# Sur_control.net
KiCad netlist of a schematic drawn in EAGLE
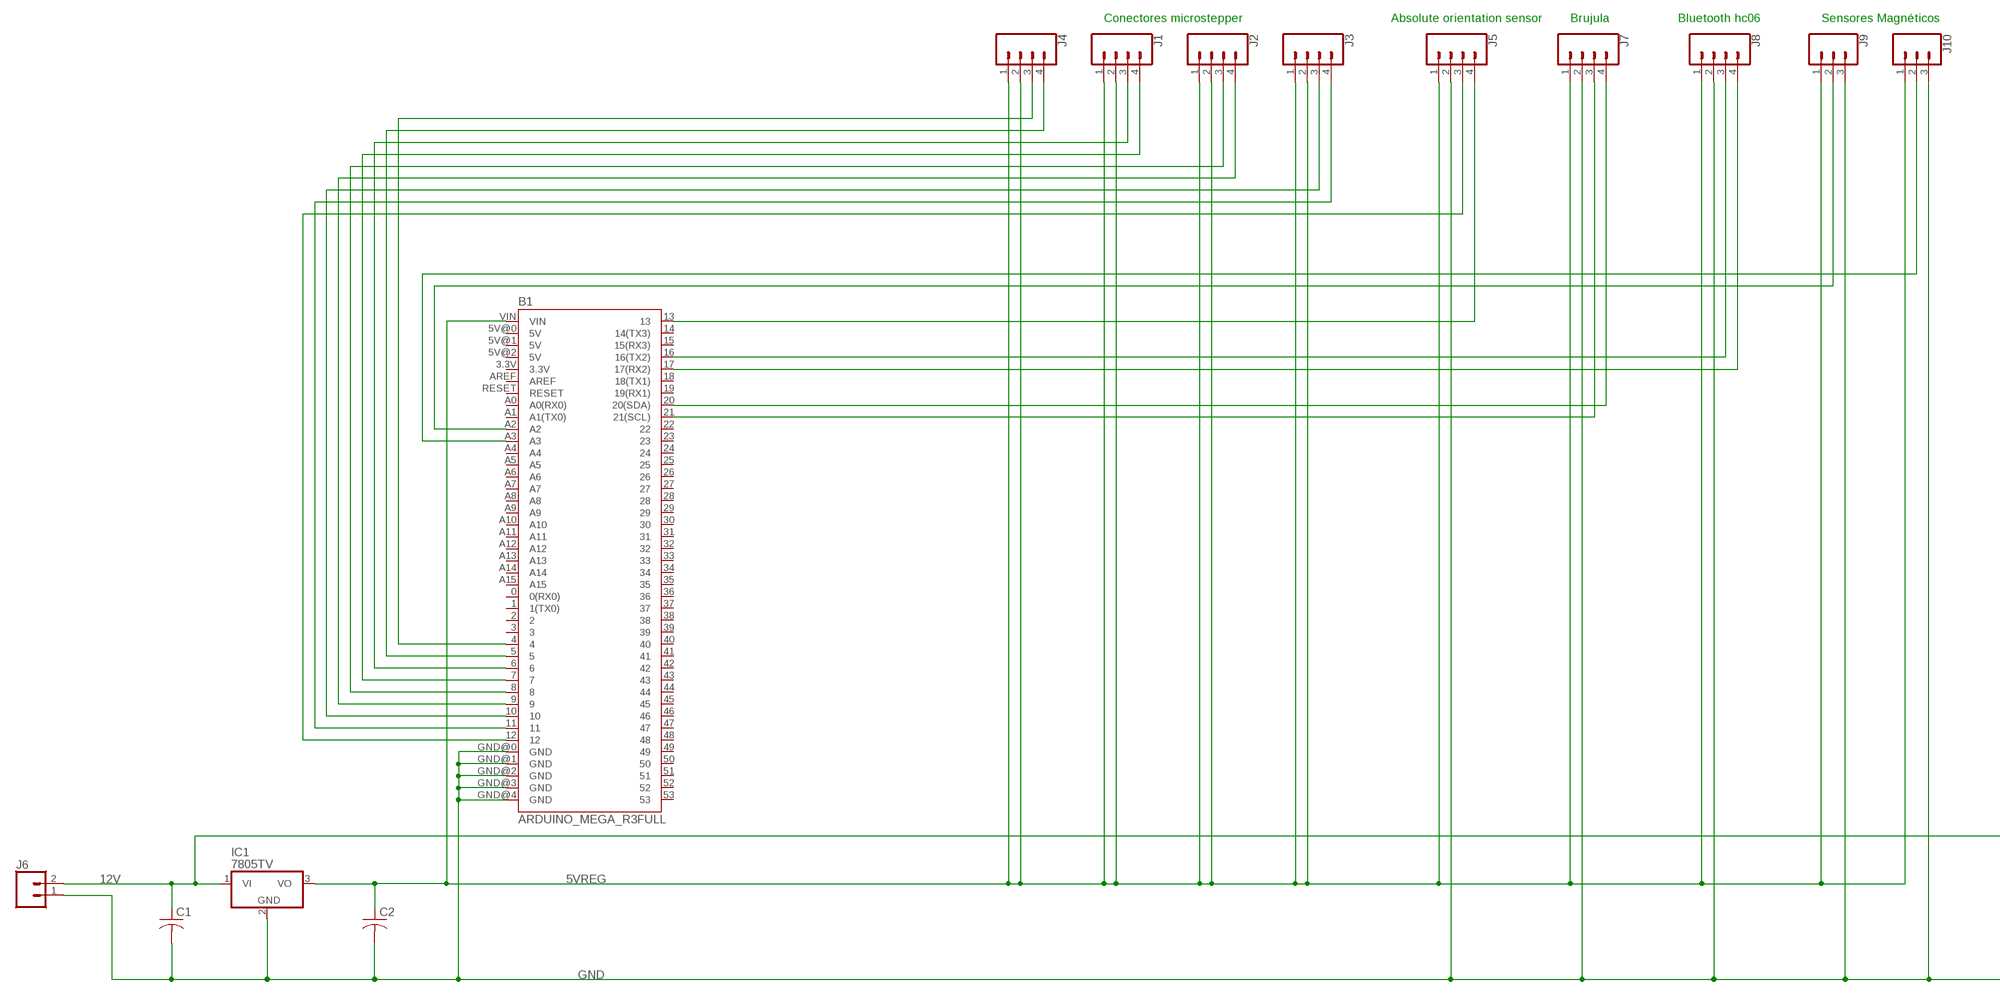
[diagram p0: schematic, sheet 1, part 1 of 2]
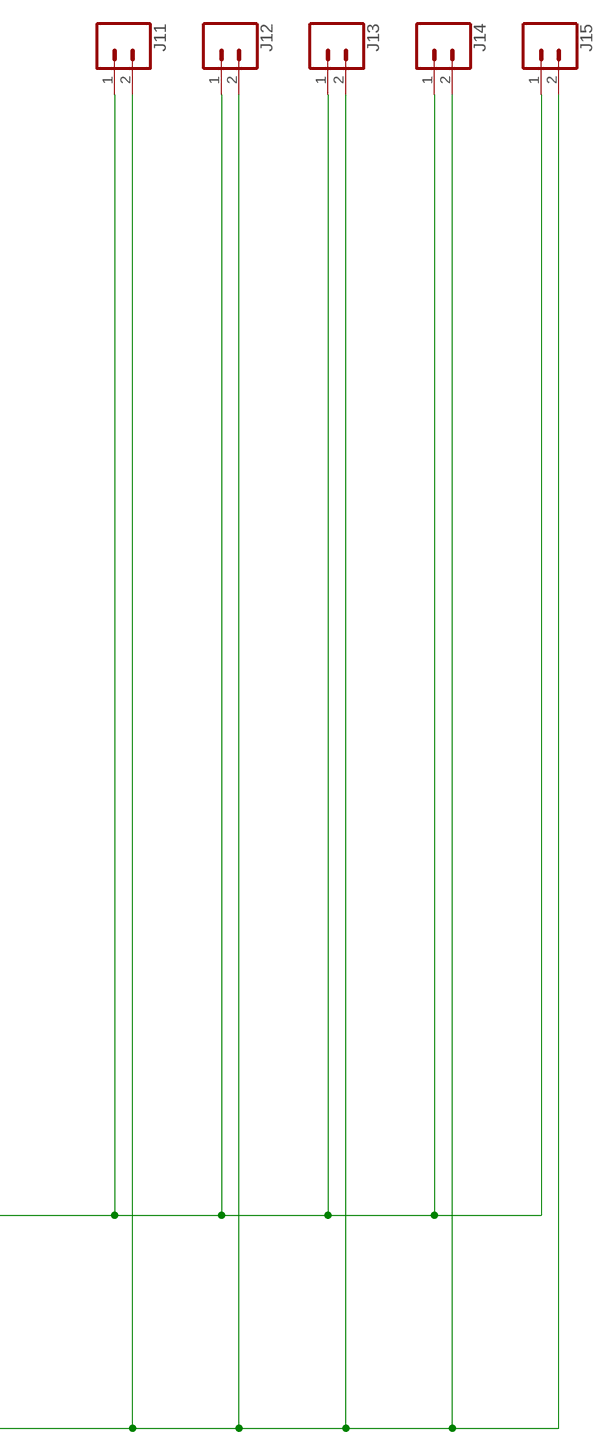
[diagram p1: schematic, sheet 1, part 2 of 2]

(export (version "E")
  (design (tool "Eeschema 10.0.6"))
  (components
    (comp (ref "B1")
      (value "ARDUINO_MEGA_R3FULL")
      (footprint "eagle-import:ARDUINO_MEGA")
      (libsource (lib "eagle-import") (part "ARDUINO_MEGA_R3FULL"))
    )
    (comp (ref "C1")
      (value "C-US050-025X075")
      (footprint "eagle-import:C050-025X075")
      (libsource (lib "eagle-import") (part "C-US050-025X075"))
    )
    (comp (ref "C2")
      (value "C-US050-025X075")
      (footprint "eagle-import:C050-025X075")
      (libsource (lib "eagle-import") (part "C-US050-025X075"))
    )
    (comp (ref "IC1")
      (value "7805TV")
      (footprint "eagle-import:TO220V")
      (libsource (lib "eagle-import") (part "78TV05"))
    )
    (comp (ref "J1")
      (value "CONN_04SCREW_LOCK")
      (footprint "eagle-import:SCREWTERMINAL-3.5MM-4_LOCK")
      (libsource (lib "eagle-import") (part "CONN_04SCREW_LOCK"))
    )
    (comp (ref "J2")
      (value "CONN_04SCREW_LOCK")
      (footprint "eagle-import:SCREWTERMINAL-3.5MM-4_LOCK")
      (libsource (lib "eagle-import") (part "CONN_04SCREW_LOCK"))
    )
    (comp (ref "J3")
      (value "CONN_04SCREW_LOCK")
      (footprint "eagle-import:SCREWTERMINAL-3.5MM-4_LOCK")
      (libsource (lib "eagle-import") (part "CONN_04SCREW_LOCK"))
    )
    (comp (ref "J4")
      (value "CONN_04SCREW_LOCK")
      (footprint "eagle-import:SCREWTERMINAL-3.5MM-4_LOCK")
      (libsource (lib "eagle-import") (part "CONN_04SCREW_LOCK"))
    )
    (comp (ref "J5")
      (value "CONN_04SCREW_LOCK")
      (footprint "eagle-import:SCREWTERMINAL-3.5MM-4_LOCK")
      (libsource (lib "eagle-import") (part "CONN_04SCREW_LOCK"))
    )
    (comp (ref "J6")
      (value "CONN_023.5MM_LOCK")
      (footprint "eagle-import:SCREWTERMINAL-3.5MM-2_LOCK")
      (libsource (lib "eagle-import") (part "CONN_023.5MM_LOCK"))
    )
    (comp (ref "J7")
      (value "CONN_04SCREW_LOCK")
      (footprint "eagle-import:SCREWTERMINAL-3.5MM-4_LOCK")
      (libsource (lib "eagle-import") (part "CONN_04SCREW_LOCK"))
    )
    (comp (ref "J8")
      (value "CONN_04SCREW_LOCK")
      (footprint "eagle-import:SCREWTERMINAL-3.5MM-4_LOCK")
      (libsource (lib "eagle-import") (part "CONN_04SCREW_LOCK"))
    )
    (comp (ref "J9")
      (value "CONN_03SCREW_LOCK")
      (footprint "eagle-import:SCREWTERMINAL-3.5MM-3_LOCK.007S")
      (libsource (lib "eagle-import") (part "CONN_03SCREW_LOCK"))
    )
    (comp (ref "J10")
      (value "CONN_03SCREW_LOCK")
      (footprint "eagle-import:SCREWTERMINAL-3.5MM-3_LOCK.007S")
      (libsource (lib "eagle-import") (part "CONN_03SCREW_LOCK"))
    )
    (comp (ref "J11")
      (value "CONN_023.5MM_LOCK")
      (footprint "eagle-import:SCREWTERMINAL-3.5MM-2_LOCK")
      (libsource (lib "eagle-import") (part "CONN_023.5MM_LOCK"))
    )
    (comp (ref "J12")
      (value "CONN_023.5MM_LOCK")
      (footprint "eagle-import:SCREWTERMINAL-3.5MM-2_LOCK")
      (libsource (lib "eagle-import") (part "CONN_023.5MM_LOCK"))
    )
    (comp (ref "J13")
      (value "CONN_023.5MM_LOCK")
      (footprint "eagle-import:SCREWTERMINAL-3.5MM-2_LOCK")
      (libsource (lib "eagle-import") (part "CONN_023.5MM_LOCK"))
    )
    (comp (ref "J14")
      (value "CONN_023.5MM_LOCK")
      (footprint "eagle-import:SCREWTERMINAL-3.5MM-2_LOCK")
      (libsource (lib "eagle-import") (part "CONN_023.5MM_LOCK"))
    )
    (comp (ref "J15")
      (value "CONN_023.5MM_LOCK")
      (footprint "eagle-import:SCREWTERMINAL-3.5MM-2_LOCK")
      (libsource (lib "eagle-import") (part "CONN_023.5MM_LOCK"))
    )
  )
  (nets
    (net (code "1") (name "/5VREG") (class "Default")
      (node (ref "B1") (pin "VIN") (pinfunction "VIN_VIN") (pintype "bidirectional"))
      (node (ref "C2") (pin "1") (pinfunction "1_1") (pintype "passive"))
      (node (ref "IC1") (pin "3") (pinfunction "VO_3") (pintype "passive"))
      (node (ref "J1") (pin "1") (pinfunction "1_1") (pintype "passive"))
      (node (ref "J1") (pin "2") (pinfunction "2_2") (pintype "passive"))
      (node (ref "J10") (pin "1") (pinfunction "1_1") (pintype "passive"))
      (node (ref "J2") (pin "1") (pinfunction "1_1") (pintype "passive"))
      (node (ref "J2") (pin "2") (pinfunction "2_2") (pintype "passive"))
      (node (ref "J3") (pin "1") (pinfunction "1_1") (pintype "passive"))
      (node (ref "J3") (pin "2") (pinfunction "2_2") (pintype "passive"))
      (node (ref "J4") (pin "1") (pinfunction "1_1") (pintype "passive"))
      (node (ref "J4") (pin "2") (pinfunction "2_2") (pintype "passive"))
      (node (ref "J5") (pin "1") (pinfunction "1_1") (pintype "passive"))
      (node (ref "J7") (pin "1") (pinfunction "1_1") (pintype "passive"))
      (node (ref "J8") (pin "1") (pinfunction "1_1") (pintype "passive"))
      (node (ref "J9") (pin "1") (pinfunction "1_1") (pintype "passive"))
    )
    (net (code "2") (name "/12V") (class "Default")
      (node (ref "C1") (pin "1") (pinfunction "1_1") (pintype "passive"))
      (node (ref "IC1") (pin "1") (pinfunction "VI_1") (pintype "input"))
      (node (ref "J11") (pin "1") (pinfunction "1_1") (pintype "passive"))
      (node (ref "J12") (pin "1") (pinfunction "1_1") (pintype "passive"))
      (node (ref "J13") (pin "1") (pinfunction "1_1") (pintype "passive"))
      (node (ref "J14") (pin "1") (pinfunction "1_1") (pintype "passive"))
      (node (ref "J15") (pin "1") (pinfunction "1_1") (pintype "passive"))
      (node (ref "J6") (pin "2") (pinfunction "2_2") (pintype "passive"))
    )
    (net (code "3") (name "/GND") (class "Default")
      (node (ref "B1") (pin "GND@0") (pinfunction "GND_GND@0") (pintype "bidirectional"))
      (node (ref "B1") (pin "GND@1") (pinfunction "GND_GND@1") (pintype "bidirectional"))
      (node (ref "B1") (pin "GND@2") (pinfunction "GND_GND@2") (pintype "bidirectional"))
      (node (ref "B1") (pin "GND@3") (pinfunction "GND_GND@3") (pintype "bidirectional"))
      (node (ref "B1") (pin "GND@4") (pinfunction "GND_GND@4") (pintype "bidirectional"))
      (node (ref "C1") (pin "2") (pinfunction "2_2") (pintype "passive"))
      (node (ref "C2") (pin "2") (pinfunction "2_2") (pintype "passive"))
      (node (ref "IC1") (pin "2") (pinfunction "GND_2") (pintype "passive"))
      (node (ref "J10") (pin "3") (pinfunction "3_3") (pintype "passive"))
      (node (ref "J11") (pin "2") (pinfunction "2_2") (pintype "passive"))
      (node (ref "J12") (pin "2") (pinfunction "2_2") (pintype "passive"))
      (node (ref "J13") (pin "2") (pinfunction "2_2") (pintype "passive"))
      (node (ref "J14") (pin "2") (pinfunction "2_2") (pintype "passive"))
      (node (ref "J15") (pin "2") (pinfunction "2_2") (pintype "passive"))
      (node (ref "J5") (pin "2") (pinfunction "2_2") (pintype "passive"))
      (node (ref "J6") (pin "1") (pinfunction "1_1") (pintype "passive"))
      (node (ref "J7") (pin "2") (pinfunction "2_2") (pintype "passive"))
      (node (ref "J8") (pin "2") (pinfunction "2_2") (pintype "passive"))
      (node (ref "J9") (pin "3") (pinfunction "3_3") (pintype "passive"))
    )
    (net (code "4") (name "Net-(B1-16(TX2))") (class "Default")
      (node (ref "B1") (pin "16") (pinfunction "16(TX2)_16") (pintype "bidirectional"))
      (node (ref "J8") (pin "3") (pinfunction "3_3") (pintype "passive"))
    )
    (net (code "5") (name "Net-(B1-17(RX2))") (class "Default")
      (node (ref "B1") (pin "17") (pinfunction "17(RX2)_17") (pintype "bidirectional"))
      (node (ref "J8") (pin "4") (pinfunction "4_4") (pintype "passive"))
    )
    (net (code "6") (name "Net-(B1-20(SDA))") (class "Default")
      (node (ref "B1") (pin "20") (pinfunction "20(SDA)_20") (pintype "bidirectional"))
      (node (ref "J7") (pin "4") (pinfunction "4_4") (pintype "passive"))
    )
    (net (code "7") (name "Net-(B1-21(SCL))") (class "Default")
      (node (ref "B1") (pin "21") (pinfunction "21(SCL)_21") (pintype "bidirectional"))
      (node (ref "J7") (pin "3") (pinfunction "3_3") (pintype "passive"))
    )
    (net (code "8") (name "Net-(B1-Pad4)") (class "Default")
      (node (ref "B1") (pin "4") (pinfunction "4_4") (pintype "bidirectional"))
      (node (ref "J4") (pin "3") (pinfunction "3_3") (pintype "passive"))
    )
    (net (code "9") (name "Net-(B1-Pad5)") (class "Default")
      (node (ref "B1") (pin "5") (pinfunction "5_5") (pintype "bidirectional"))
      (node (ref "J4") (pin "4") (pinfunction "4_4") (pintype "passive"))
    )
    (net (code "10") (name "Net-(B1-Pad6)") (class "Default")
      (node (ref "B1") (pin "6") (pinfunction "6_6") (pintype "bidirectional"))
      (node (ref "J1") (pin "3") (pinfunction "3_3") (pintype "passive"))
    )
    (net (code "11") (name "Net-(B1-Pad7)") (class "Default")
      (node (ref "B1") (pin "7") (pinfunction "7_7") (pintype "bidirectional"))
      (node (ref "J1") (pin "4") (pinfunction "4_4") (pintype "passive"))
    )
    (net (code "12") (name "Net-(B1-Pad8)") (class "Default")
      (node (ref "B1") (pin "8") (pinfunction "8_8") (pintype "bidirectional"))
      (node (ref "J2") (pin "3") (pinfunction "3_3") (pintype "passive"))
    )
    (net (code "13") (name "Net-(B1-Pad9)") (class "Default")
      (node (ref "B1") (pin "9") (pinfunction "9_9") (pintype "bidirectional"))
      (node (ref "J2") (pin "4") (pinfunction "4_4") (pintype "passive"))
    )
    (net (code "14") (name "Net-(B1-Pad10)") (class "Default")
      (node (ref "B1") (pin "10") (pinfunction "10_10") (pintype "bidirectional"))
      (node (ref "J3") (pin "3") (pinfunction "3_3") (pintype "passive"))
    )
    (net (code "15") (name "Net-(B1-Pad11)") (class "Default")
      (node (ref "B1") (pin "11") (pinfunction "11_11") (pintype "bidirectional"))
      (node (ref "J3") (pin "4") (pinfunction "4_4") (pintype "passive"))
    )
    (net (code "16") (name "Net-(B1-Pad12)") (class "Default")
      (node (ref "B1") (pin "12") (pinfunction "12_12") (pintype "bidirectional"))
      (node (ref "J5") (pin "3") (pinfunction "3_3") (pintype "passive"))
    )
    (net (code "17") (name "Net-(B1-Pad13)") (class "Default")
      (node (ref "B1") (pin "13") (pinfunction "13_13") (pintype "bidirectional"))
      (node (ref "J5") (pin "4") (pinfunction "4_4") (pintype "passive"))
    )
    (net (code "18") (name "Net-(B1-PadA2)") (class "Default")
      (node (ref "B1") (pin "A2") (pinfunction "A2_A2") (pintype "bidirectional"))
      (node (ref "J9") (pin "2") (pinfunction "2_2") (pintype "passive"))
    )
    (net (code "19") (name "Net-(B1-PadA3)") (class "Default")
      (node (ref "B1") (pin "A3") (pinfunction "A3_A3") (pintype "bidirectional"))
      (node (ref "J10") (pin "2") (pinfunction "2_2") (pintype "passive"))
    )
    (net (code "20") (name "unconnected-(B1-0(RX0)-Pad0)") (class "Default")
      (node (ref "B1") (pin "0") (pinfunction "0(RX0)_0") (pintype "bidirectional"))
    )
    (net (code "21") (name "unconnected-(B1-1(TX0)-Pad1)") (class "Default")
      (node (ref "B1") (pin "1") (pinfunction "1(TX0)_1") (pintype "bidirectional"))
    )
    (net (code "22") (name "unconnected-(B1-5V-Pad5V@0)") (class "Default")
      (node (ref "B1") (pin "5V@0") (pinfunction "5V_5V@0") (pintype "bidirectional"))
    )
    (net (code "23") (name "unconnected-(B1-5V-Pad5V@1)") (class "Default")
      (node (ref "B1") (pin "5V@1") (pinfunction "5V_5V@1") (pintype "bidirectional"))
    )
    (net (code "24") (name "unconnected-(B1-5V-Pad5V@2)") (class "Default")
      (node (ref "B1") (pin "5V@2") (pinfunction "5V_5V@2") (pintype "bidirectional"))
    )
    (net (code "25") (name "unconnected-(B1-14(TX3)-Pad14)") (class "Default")
      (node (ref "B1") (pin "14") (pinfunction "14(TX3)_14") (pintype "bidirectional"))
    )
    (net (code "26") (name "unconnected-(B1-15(RX3)-Pad15)") (class "Default")
      (node (ref "B1") (pin "15") (pinfunction "15(RX3)_15") (pintype "bidirectional"))
    )
    (net (code "27") (name "unconnected-(B1-18(TX1)-Pad18)") (class "Default")
      (node (ref "B1") (pin "18") (pinfunction "18(TX1)_18") (pintype "bidirectional"))
    )
    (net (code "28") (name "unconnected-(B1-19(RX1)-Pad19)") (class "Default")
      (node (ref "B1") (pin "19") (pinfunction "19(RX1)_19") (pintype "bidirectional"))
    )
    (net (code "29") (name "unconnected-(B1-A0(RX0)-PadA0)") (class "Default")
      (node (ref "B1") (pin "A0") (pinfunction "A0(RX0)_A0") (pintype "bidirectional"))
    )
    (net (code "30") (name "unconnected-(B1-A1(TX0)-PadA1)") (class "Default")
      (node (ref "B1") (pin "A1") (pinfunction "A1(TX0)_A1") (pintype "bidirectional"))
    )
    (net (code "31") (name "unconnected-(B1-Pad2)") (class "Default")
      (node (ref "B1") (pin "2") (pinfunction "2_2") (pintype "bidirectional"))
    )
    (net (code "32") (name "unconnected-(B1-Pad3)") (class "Default")
      (node (ref "B1") (pin "3") (pinfunction "3_3") (pintype "bidirectional"))
    )
    (net (code "33") (name "unconnected-(B1-Pad3.3V)") (class "Default")
      (node (ref "B1") (pin "3.3V") (pinfunction "3.3V_3.3V") (pintype "bidirectional"))
    )
    (net (code "34") (name "unconnected-(B1-Pad22)") (class "Default")
      (node (ref "B1") (pin "22") (pinfunction "22_22") (pintype "bidirectional"))
    )
    (net (code "35") (name "unconnected-(B1-Pad23)") (class "Default")
      (node (ref "B1") (pin "23") (pinfunction "23_23") (pintype "bidirectional"))
    )
    (net (code "36") (name "unconnected-(B1-Pad24)") (class "Default")
      (node (ref "B1") (pin "24") (pinfunction "24_24") (pintype "bidirectional"))
    )
    (net (code "37") (name "unconnected-(B1-Pad25)") (class "Default")
      (node (ref "B1") (pin "25") (pinfunction "25_25") (pintype "bidirectional"))
    )
    (net (code "38") (name "unconnected-(B1-Pad26)") (class "Default")
      (node (ref "B1") (pin "26") (pinfunction "26_26") (pintype "bidirectional"))
    )
    (net (code "39") (name "unconnected-(B1-Pad27)") (class "Default")
      (node (ref "B1") (pin "27") (pinfunction "27_27") (pintype "bidirectional"))
    )
    (net (code "40") (name "unconnected-(B1-Pad28)") (class "Default")
      (node (ref "B1") (pin "28") (pinfunction "28_28") (pintype "bidirectional"))
    )
    (net (code "41") (name "unconnected-(B1-Pad29)") (class "Default")
      (node (ref "B1") (pin "29") (pinfunction "29_29") (pintype "bidirectional"))
    )
    (net (code "42") (name "unconnected-(B1-Pad30)") (class "Default")
      (node (ref "B1") (pin "30") (pinfunction "30_30") (pintype "bidirectional"))
    )
    (net (code "43") (name "unconnected-(B1-Pad31)") (class "Default")
      (node (ref "B1") (pin "31") (pinfunction "31_31") (pintype "bidirectional"))
    )
    (net (code "44") (name "unconnected-(B1-Pad32)") (class "Default")
      (node (ref "B1") (pin "32") (pinfunction "32_32") (pintype "bidirectional"))
    )
    (net (code "45") (name "unconnected-(B1-Pad33)") (class "Default")
      (node (ref "B1") (pin "33") (pinfunction "33_33") (pintype "bidirectional"))
    )
    (net (code "46") (name "unconnected-(B1-Pad34)") (class "Default")
      (node (ref "B1") (pin "34") (pinfunction "34_34") (pintype "bidirectional"))
    )
    (net (code "47") (name "unconnected-(B1-Pad35)") (class "Default")
      (node (ref "B1") (pin "35") (pinfunction "35_35") (pintype "bidirectional"))
    )
    (net (code "48") (name "unconnected-(B1-Pad36)") (class "Default")
      (node (ref "B1") (pin "36") (pinfunction "36_36") (pintype "bidirectional"))
    )
    (net (code "49") (name "unconnected-(B1-Pad37)") (class "Default")
      (node (ref "B1") (pin "37") (pinfunction "37_37") (pintype "bidirectional"))
    )
    (net (code "50") (name "unconnected-(B1-Pad38)") (class "Default")
      (node (ref "B1") (pin "38") (pinfunction "38_38") (pintype "bidirectional"))
    )
    (net (code "51") (name "unconnected-(B1-Pad39)") (class "Default")
      (node (ref "B1") (pin "39") (pinfunction "39_39") (pintype "bidirectional"))
    )
    (net (code "52") (name "unconnected-(B1-Pad40)") (class "Default")
      (node (ref "B1") (pin "40") (pinfunction "40_40") (pintype "bidirectional"))
    )
    (net (code "53") (name "unconnected-(B1-Pad41)") (class "Default")
      (node (ref "B1") (pin "41") (pinfunction "41_41") (pintype "bidirectional"))
    )
    (net (code "54") (name "unconnected-(B1-Pad42)") (class "Default")
      (node (ref "B1") (pin "42") (pinfunction "42_42") (pintype "bidirectional"))
    )
    (net (code "55") (name "unconnected-(B1-Pad43)") (class "Default")
      (node (ref "B1") (pin "43") (pinfunction "43_43") (pintype "bidirectional"))
    )
    (net (code "56") (name "unconnected-(B1-Pad44)") (class "Default")
      (node (ref "B1") (pin "44") (pinfunction "44_44") (pintype "bidirectional"))
    )
    (net (code "57") (name "unconnected-(B1-Pad45)") (class "Default")
      (node (ref "B1") (pin "45") (pinfunction "45_45") (pintype "bidirectional"))
    )
    (net (code "58") (name "unconnected-(B1-Pad46)") (class "Default")
      (node (ref "B1") (pin "46") (pinfunction "46_46") (pintype "bidirectional"))
    )
    (net (code "59") (name "unconnected-(B1-Pad47)") (class "Default")
      (node (ref "B1") (pin "47") (pinfunction "47_47") (pintype "bidirectional"))
    )
    (net (code "60") (name "unconnected-(B1-Pad48)") (class "Default")
      (node (ref "B1") (pin "48") (pinfunction "48_48") (pintype "bidirectional"))
    )
    (net (code "61") (name "unconnected-(B1-Pad49)") (class "Default")
      (node (ref "B1") (pin "49") (pinfunction "49_49") (pintype "bidirectional"))
    )
    (net (code "62") (name "unconnected-(B1-Pad50)") (class "Default")
      (node (ref "B1") (pin "50") (pinfunction "50_50") (pintype "bidirectional"))
    )
    (net (code "63") (name "unconnected-(B1-Pad51)") (class "Default")
      (node (ref "B1") (pin "51") (pinfunction "51_51") (pintype "bidirectional"))
    )
    (net (code "64") (name "unconnected-(B1-Pad52)") (class "Default")
      (node (ref "B1") (pin "52") (pinfunction "52_52") (pintype "bidirectional"))
    )
    (net (code "65") (name "unconnected-(B1-Pad53)") (class "Default")
      (node (ref "B1") (pin "53") (pinfunction "53_53") (pintype "bidirectional"))
    )
    (net (code "66") (name "unconnected-(B1-PadA4)") (class "Default")
      (node (ref "B1") (pin "A4") (pinfunction "A4_A4") (pintype "bidirectional"))
    )
    (net (code "67") (name "unconnected-(B1-PadA5)") (class "Default")
      (node (ref "B1") (pin "A5") (pinfunction "A5_A5") (pintype "bidirectional"))
    )
    (net (code "68") (name "unconnected-(B1-PadA6)") (class "Default")
      (node (ref "B1") (pin "A6") (pinfunction "A6_A6") (pintype "bidirectional"))
    )
    (net (code "69") (name "unconnected-(B1-PadA7)") (class "Default")
      (node (ref "B1") (pin "A7") (pinfunction "A7_A7") (pintype "bidirectional"))
    )
    (net (code "70") (name "unconnected-(B1-PadA8)") (class "Default")
      (node (ref "B1") (pin "A8") (pinfunction "A8_A8") (pintype "bidirectional"))
    )
    (net (code "71") (name "unconnected-(B1-PadA9)") (class "Default")
      (node (ref "B1") (pin "A9") (pinfunction "A9_A9") (pintype "bidirectional"))
    )
    (net (code "72") (name "unconnected-(B1-PadA10)") (class "Default")
      (node (ref "B1") (pin "A10") (pinfunction "A10_A10") (pintype "bidirectional"))
    )
    (net (code "73") (name "unconnected-(B1-PadA11)") (class "Default")
      (node (ref "B1") (pin "A11") (pinfunction "A11_A11") (pintype "bidirectional"))
    )
    (net (code "74") (name "unconnected-(B1-PadA12)") (class "Default")
      (node (ref "B1") (pin "A12") (pinfunction "A12_A12") (pintype "bidirectional"))
    )
    (net (code "75") (name "unconnected-(B1-PadA13)") (class "Default")
      (node (ref "B1") (pin "A13") (pinfunction "A13_A13") (pintype "bidirectional"))
    )
    (net (code "76") (name "unconnected-(B1-PadA14)") (class "Default")
      (node (ref "B1") (pin "A14") (pinfunction "A14_A14") (pintype "bidirectional"))
    )
    (net (code "77") (name "unconnected-(B1-PadA15)") (class "Default")
      (node (ref "B1") (pin "A15") (pinfunction "A15_A15") (pintype "bidirectional"))
    )
    (net (code "78") (name "unconnected-(B1-PadAREF)") (class "Default")
      (node (ref "B1") (pin "AREF") (pinfunction "AREF_AREF") (pintype "bidirectional"))
    )
    (net (code "79") (name "unconnected-(B1-PadRESET)") (class "Default")
      (node (ref "B1") (pin "RESET") (pinfunction "RESET_RESET") (pintype "bidirectional"))
    )
  )
)
